# CAN.net
KiCad netlist of a schematic drawn in Altium Designer
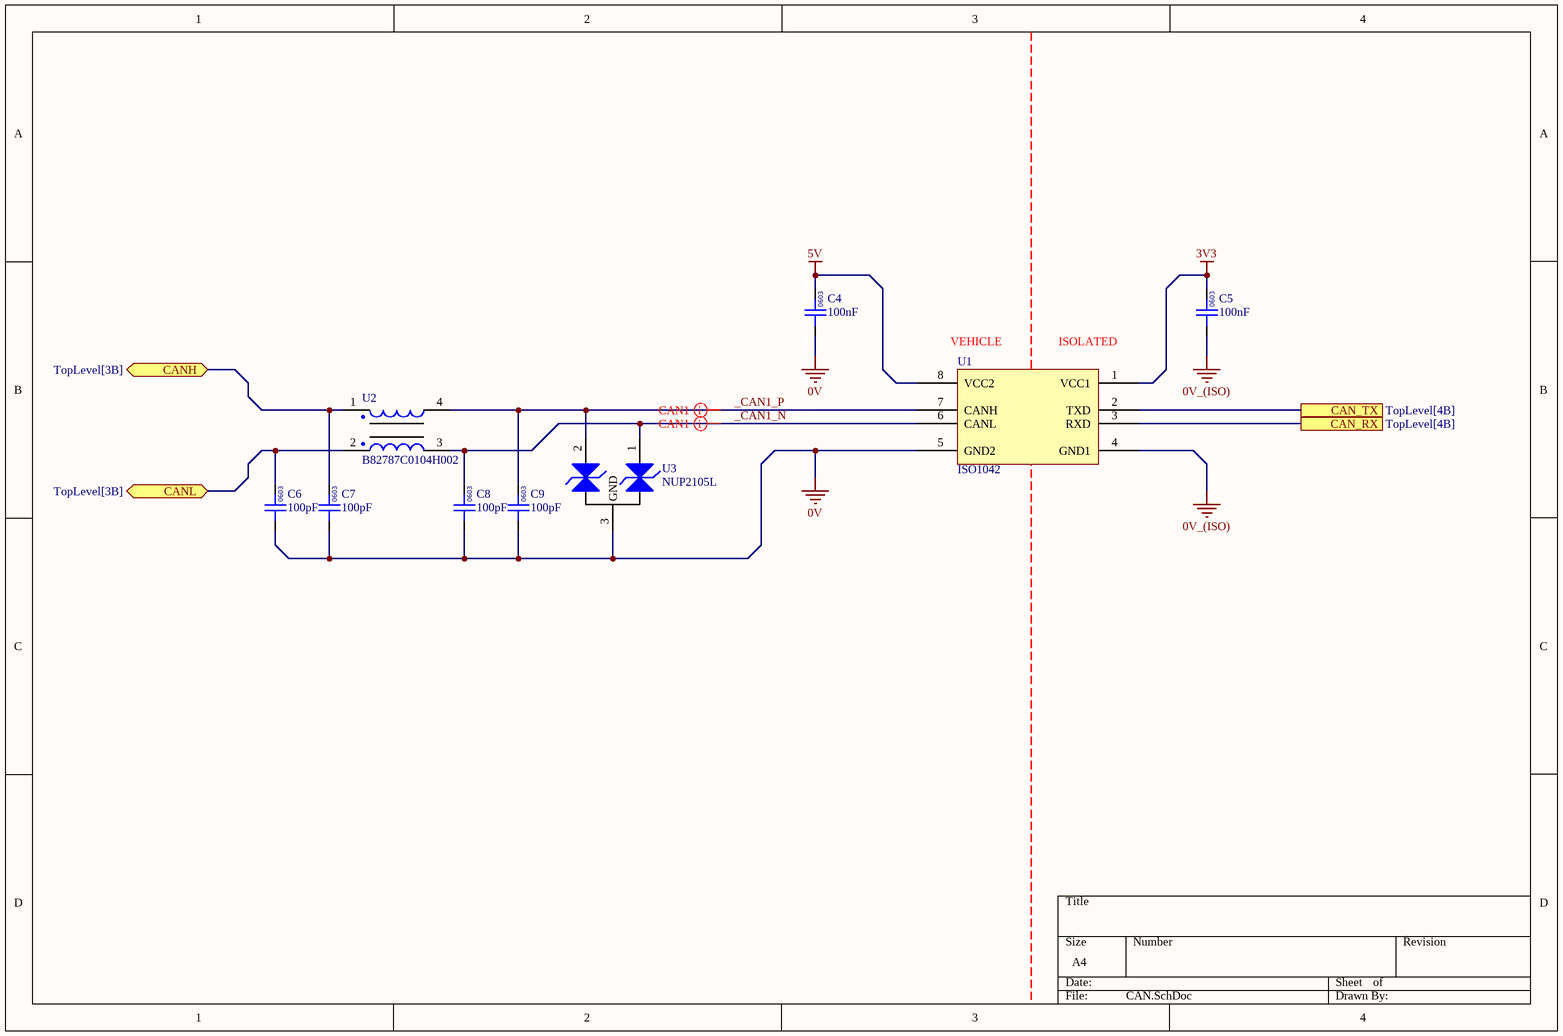
[diagram p0: CAN.SchDoc]

(export (version "E")
  (design (tool "Eeschema 10.0.6"))
  (components
    (comp (ref "C4")
      (value "100nF")
      (footprint "0603")
      (fields
        (field (name "PART NUMBER") "GCM188L81H104KA57D")
        (field (name "MANUFACTURER") "muRata")
        (field (name "TOLERANCE") "±10%")
      )
      (libsource (lib "ts_standard_library") (part "Capacitor 0603"))
    )
    (comp (ref "C5")
      (value "100nF")
      (footprint "0603")
      (fields
        (field (name "PART NUMBER") "GCM188L81H104KA57D")
        (field (name "MANUFACTURER") "muRata")
        (field (name "TOLERANCE") "±10%")
      )
      (libsource (lib "ts_standard_library") (part "Capacitor 0603"))
    )
    (comp (ref "C6")
      (value "100pF")
      (footprint "0603")
      (fields
        (field (name "PART NUMBER") "GRM1885C1H101JA01D")
        (field (name "MANUFACTURER") "Murata Electronics")
        (field (name "TOLERANCE") "±5%")
      )
      (libsource (lib "ts_standard_library") (part "Capacitor 0603"))
    )
    (comp (ref "C7")
      (value "100pF")
      (footprint "0603")
      (fields
        (field (name "PART NUMBER") "GRM1885C1H101JA01D")
        (field (name "MANUFACTURER") "Murata Electronics")
        (field (name "TOLERANCE") "±5%")
      )
      (libsource (lib "ts_standard_library") (part "Capacitor 0603"))
    )
    (comp (ref "C8")
      (value "100pF")
      (footprint "0603")
      (fields
        (field (name "PART NUMBER") "GRM1885C1H101JA01D")
        (field (name "MANUFACTURER") "Murata Electronics")
        (field (name "TOLERANCE") "±5%")
      )
      (libsource (lib "ts_standard_library") (part "Capacitor 0603"))
    )
    (comp (ref "C9")
      (value "100pF")
      (footprint "0603")
      (fields
        (field (name "PART NUMBER") "GRM1885C1H101JA01D")
        (field (name "MANUFACTURER") "Murata Electronics")
        (field (name "TOLERANCE") "±5%")
      )
      (libsource (lib "ts_standard_library") (part "Capacitor 0603"))
    )
    (comp (ref "U1")
      (value "ISO1042")
      (footprint "TI-SOIC-8")
      (description "IC CAN TRANSCEIVER 1/1 8SOIC")
      (fields
        (field (name "MANUFACTURER") "Texas Instruments")
        (field (name "DIGIKEY PART NUMBER") "296-ISO1042BQDWVQ1-ND")
      )
      (libsource (lib "ts_standard_library") (part "ISO1042"))
    )
    (comp (ref "U2")
      (value "B82787C0104H002")
      (footprint "TDK 4-PC Pad")
      (fields
        (field (name "MANUFACTURER") "EPCOS (TDK)")
        (field (name "DIGIKEY PART NUMBER") "495-4598-1-ND")
      )
      (libsource (lib "ts_standard_library") (part "B82787C0104H002"))
    )
    (comp (ref "U3")
      (value "NUP2105L")
      (footprint "ON SOT-23")
      (description "Dual Line CAN Bus Protector")
      (fields
        (field (name "MANUFACTURER") "ON Semiconductor")
        (field (name "DIGIKEY PART NUMBER") "NUP2105LT1GOSCT-ND")
      )
      (libsource (lib "ts_standard_library") (part "NUP2105L"))
    )
  )
  (nets
    (net (code "1") (name "/CANH") (class "Default")
      (node (ref "C7") (pin "2") (pinfunction "2_2") (pintype "passive"))
      (node (ref "U2") (pin "1") (pinfunction "1_1") (pintype "passive"))
    )
    (net (code "2") (name "/CANL") (class "Default")
      (node (ref "C6") (pin "2") (pinfunction "2_2") (pintype "passive"))
      (node (ref "U2") (pin "2") (pinfunction "2_2") (pintype "passive"))
    )
    (net (code "3") (name "/CAN_RX") (class "Default")
      (node (ref "U1") (pin "3") (pinfunction "RXD_3") (pintype "passive"))
    )
    (net (code "4") (name "/CAN_TX") (class "Default")
      (node (ref "U1") (pin "2") (pinfunction "TXD_2") (pintype "passive"))
    )
    (net (code "5") (name "/_CAN1_N") (class "Default")
      (node (ref "C8") (pin "2") (pinfunction "2_2") (pintype "passive"))
      (node (ref "U1") (pin "6") (pinfunction "CANL_6") (pintype "passive"))
      (node (ref "U2") (pin "3") (pinfunction "3_3") (pintype "passive"))
      (node (ref "U3") (pin "1") (pinfunction "CAN_H_1") (pintype "passive"))
    )
    (net (code "6") (name "/_CAN1_P") (class "Default")
      (node (ref "C9") (pin "2") (pinfunction "2_2") (pintype "passive"))
      (node (ref "U1") (pin "7") (pinfunction "CANH_7") (pintype "passive"))
      (node (ref "U2") (pin "4") (pinfunction "4_4") (pintype "passive"))
      (node (ref "U3") (pin "2") (pinfunction "CAN_L_2") (pintype "passive"))
    )
    (net (code "7") (name "0V") (class "Default")
      (node (ref "C4") (pin "1") (pinfunction "1_1") (pintype "passive"))
      (node (ref "C6") (pin "1") (pinfunction "1_1") (pintype "passive"))
      (node (ref "C7") (pin "1") (pinfunction "1_1") (pintype "passive"))
      (node (ref "C8") (pin "1") (pinfunction "1_1") (pintype "passive"))
      (node (ref "C9") (pin "1") (pinfunction "1_1") (pintype "passive"))
      (node (ref "U1") (pin "5") (pinfunction "GND2_5") (pintype "passive"))
      (node (ref "U3") (pin "3") (pinfunction "GND_3") (pintype "passive"))
    )
    (net (code "8") (name "0V_(ISO)") (class "Default")
      (node (ref "C5") (pin "1") (pinfunction "1_1") (pintype "passive"))
      (node (ref "U1") (pin "4") (pinfunction "GND1_4") (pintype "passive"))
    )
    (net (code "9") (name "3V3") (class "Default")
      (node (ref "C5") (pin "2") (pinfunction "2_2") (pintype "passive"))
      (node (ref "U1") (pin "1") (pinfunction "VCC1_1") (pintype "passive"))
    )
    (net (code "10") (name "5V") (class "Default")
      (node (ref "C4") (pin "2") (pinfunction "2_2") (pintype "passive"))
      (node (ref "U1") (pin "8") (pinfunction "VCC2_8") (pintype "passive"))
    )
  )
)
